# wireless-ac-motor-controller-mk-1_1.net
KiCad netlist of a schematic drawn in EAGLE
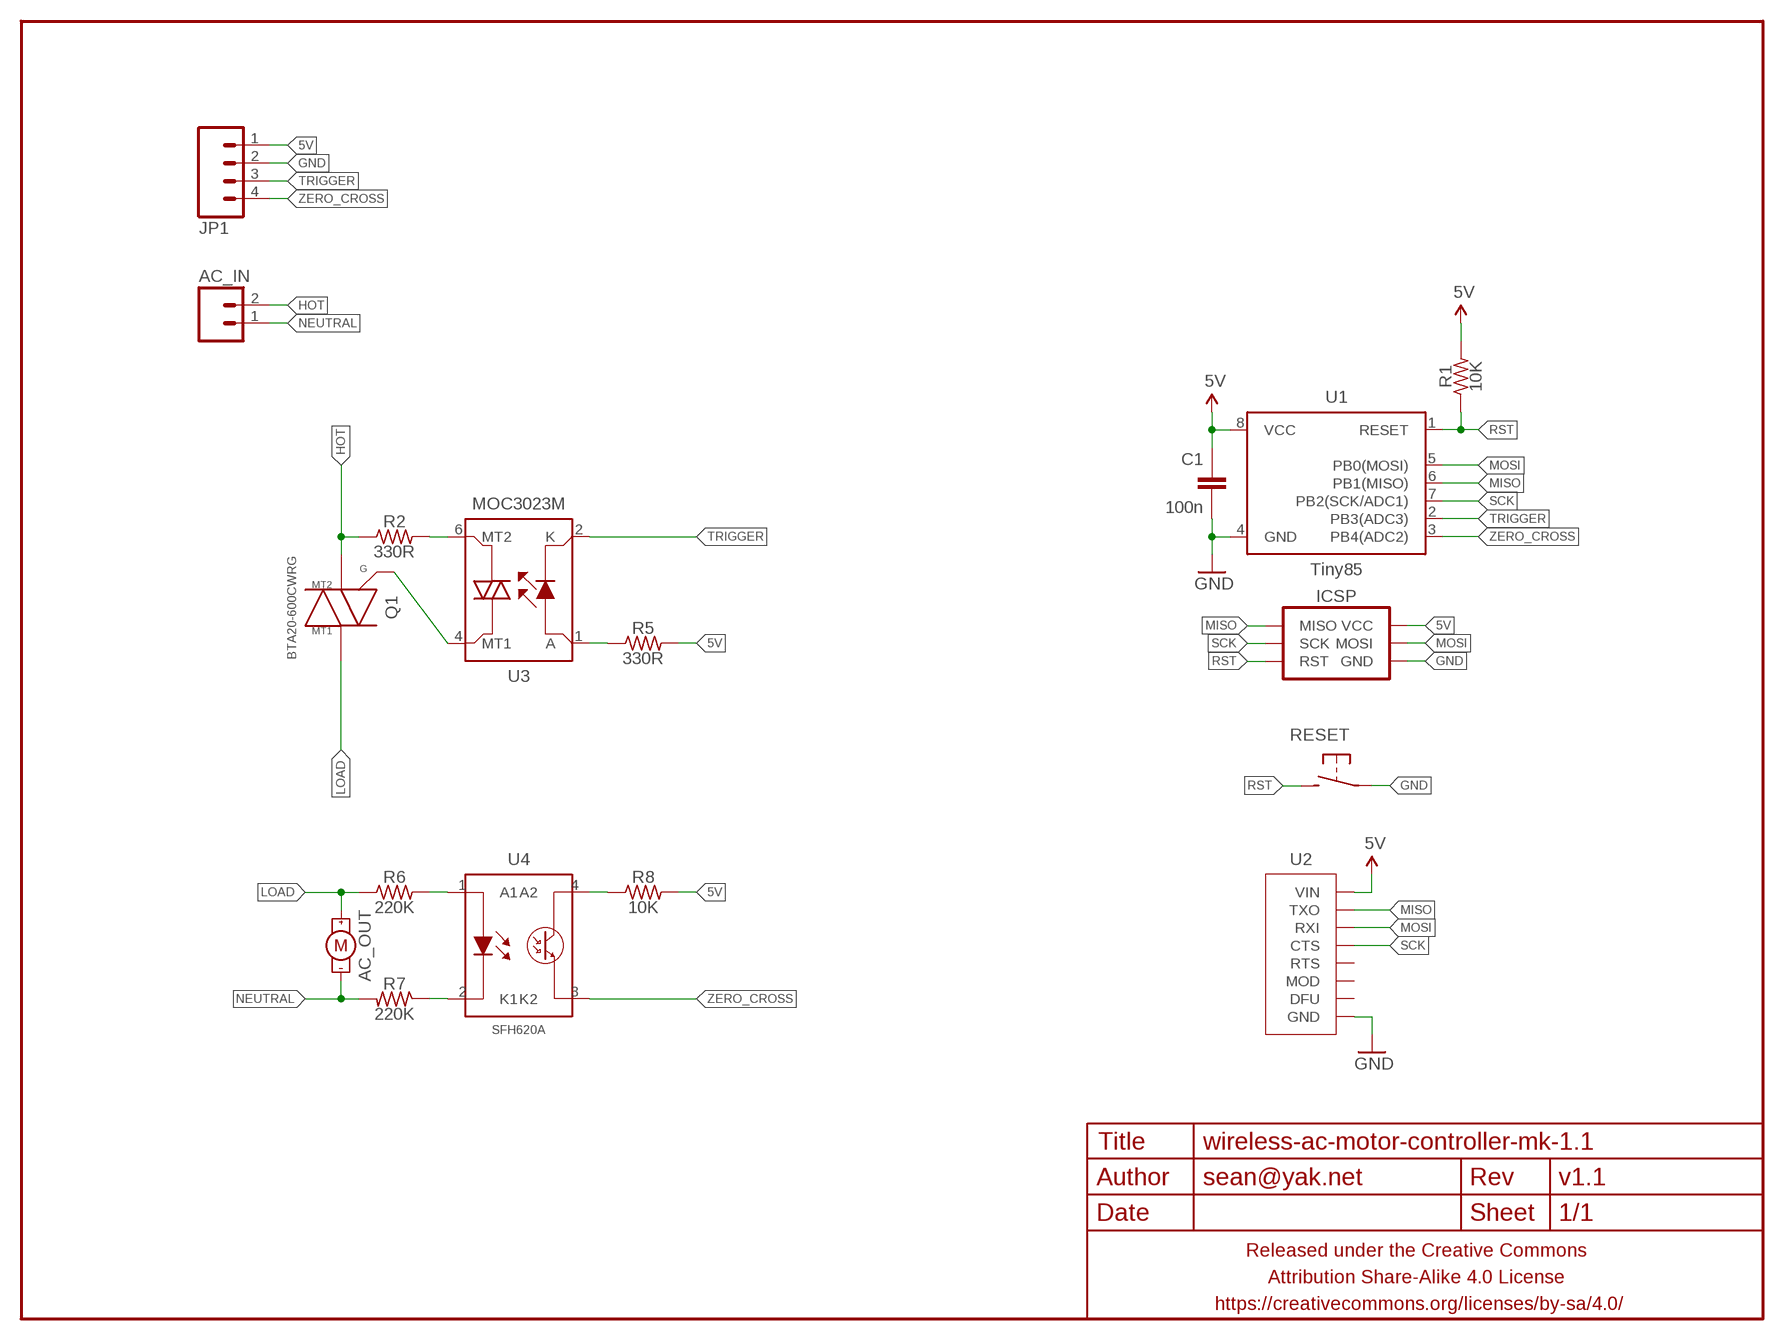
[diagram p0: schematic, sheet 1]

(export (version "E")
  (design (tool "Eeschema 10.0.6"))
  (components
    (comp (ref "AC_IN")
      (value "SCREWTERMINAL-25MM")
      (footprint "eagle-import:SCREWTERM-5MM-2")
      (libsource (lib "eagle-import") (part "SCREWTERMINAL-25MM"))
    )
    (comp (ref "AC_OUT")
      (value "MOTOR5MM-SCREW-TERM")
      (footprint "eagle-import:1X02_5MM_SCREW")
      (libsource (lib "eagle-import") (part "MOTOR5MM-SCREW-TERM"))
    )
    (comp (ref "C1")
      (value "100n")
      (footprint "eagle-import:C0805")
      (libsource (lib "eagle-import") (part "CAPACITOR-CERAMICC0805"))
    )
    (comp (ref "FRAME1")
      (value "FRAME-LETTERNO_PACKAGE")
      (footprint "eagle-import:DUMMY")
      (fields (field (name "DESIGNER") "sean@yak.net") (field (name "VERSION") "v1.1"))
      (libsource (lib "eagle-import") (part "FRAME-LETTERNO_PACKAGE"))
    )
    (comp (ref "ICSP")
      (value "AVR_SPI_PRG_6PTH")
      (footprint "eagle-import:2X3")
      (libsource (lib "eagle-import") (part "AVR_SPI_PRG_6PTH"))
    )
    (comp (ref "JP1")
      (value "M04JST-PTH-VERT")
      (footprint "eagle-import:JST-4-PH-VERT-PTH")
      (libsource (lib "eagle-import") (part "M04JST-PTH-VERT"))
    )
    (comp (ref "Q1")
      (value "BTA20-600CWRG")
      (footprint "eagle-import:TO220V")
      (libsource (lib "eagle-import") (part "TRIACTO-220-VERT"))
    )
    (comp (ref "R1")
      (value "10K")
      (footprint "eagle-import:R0805")
      (libsource (lib "eagle-import") (part "RESISTORR0805"))
    )
    (comp (ref "R2")
      (value "330R")
      (footprint "eagle-import:R0805")
      (libsource (lib "eagle-import") (part "RESISTORR0805"))
    )
    (comp (ref "R5")
      (value "330R")
      (footprint "eagle-import:R0805")
      (libsource (lib "eagle-import") (part "RESISTORR0805"))
    )
    (comp (ref "R6")
      (value "220K")
      (footprint "eagle-import:0411V")
      (libsource (lib "eagle-import") (part "RESISTOR0411/3V"))
    )
    (comp (ref "R7")
      (value "220K")
      (footprint "eagle-import:0411V")
      (libsource (lib "eagle-import") (part "RESISTOR0411/3V"))
    )
    (comp (ref "R8")
      (value "10K")
      (footprint "eagle-import:R0805")
      (libsource (lib "eagle-import") (part "RESISTORR0805"))
    )
    (comp (ref "RESET")
      (value "SPST-NO-TACT3MM-PTH-SMALL-PADS")
      (footprint "eagle-import:DTS-3-SMALL-PADS")
      (libsource (lib "eagle-import") (part "SPST-NO-TACT3MM-PTH-SMALL-PADS"))
    )
    (comp (ref "U1")
      (value "Tiny85")
      (footprint "eagle-import:SO08-EIAJ")
      (libsource (lib "eagle-import") (part "ATTINY45TINY85-20-SOICW"))
    )
    (comp (ref "U2")
      (value "ADAFRUIT_BLE_UARTBARE")
      (footprint "eagle-import:ADAFRUIT_BLE_UART")
      (libsource (lib "eagle-import") (part "ADAFRUIT_BLE_UARTBARE"))
    )
    (comp (ref "U3")
      (value "MOC3023M")
      (footprint "eagle-import:DIP06")
      (libsource (lib "eagle-import") (part "MOC30XXMOC30XXM-DIP6"))
    )
    (comp (ref "U4")
      (value "SFH620A")
      (footprint "eagle-import:DIL04")
      (libsource (lib "eagle-import") (part "OPTOISOLATORDIP4"))
    )
  )
  (nets
    (net (code "1") (name "5V") (class "Default")
      (node (ref "C1") (pin "1") (pinfunction "1_1") (pintype "passive"))
      (node (ref "ICSP") (pin "2") (pinfunction "VCC_2") (pintype "passive"))
      (node (ref "JP1") (pin "1") (pinfunction "1_1") (pintype "passive"))
      (node (ref "R1") (pin "2") (pinfunction "2_2") (pintype "passive"))
      (node (ref "R5") (pin "2") (pinfunction "2_2") (pintype "passive"))
      (node (ref "R8") (pin "2") (pinfunction "2_2") (pintype "passive"))
      (node (ref "U1") (pin "8") (pinfunction "VCC_8") (pintype "bidirectional"))
      (node (ref "U2") (pin "VIN") (pinfunction "VIN_VIN") (pintype "bidirectional"))
    )
    (net (code "2") (name "GND") (class "Default")
      (node (ref "C1") (pin "2") (pinfunction "2_2") (pintype "passive"))
      (node (ref "ICSP") (pin "6") (pinfunction "GND_6") (pintype "passive"))
      (node (ref "JP1") (pin "2") (pinfunction "2_2") (pintype "passive"))
      (node (ref "RESET") (pin "1") (pinfunction "1_1") (pintype "passive"))
      (node (ref "U1") (pin "4") (pinfunction "GND_4") (pintype "bidirectional"))
      (node (ref "U2") (pin "GND") (pinfunction "GND_GND") (pintype "bidirectional"))
    )
    (net (code "3") (name "HOT") (class "Default")
      (node (ref "AC_IN") (pin "2") (pinfunction "2_2") (pintype "passive"))
      (node (ref "Q1") (pin "2") (pinfunction "MT2_2") (pintype "bidirectional"))
      (node (ref "R2") (pin "1") (pinfunction "1_1") (pintype "passive"))
    )
    (net (code "4") (name "LOAD") (class "Default")
      (node (ref "AC_OUT") (pin "1") (pinfunction "+_1") (pintype "bidirectional"))
      (node (ref "Q1") (pin "1") (pinfunction "MT1_1") (pintype "bidirectional"))
      (node (ref "R6") (pin "1") (pinfunction "1_1") (pintype "passive"))
    )
    (net (code "5") (name "MISO") (class "Default")
      (node (ref "ICSP") (pin "1") (pinfunction "MISO_1") (pintype "passive"))
      (node (ref "U1") (pin "6") (pinfunction "PB1(MISO)_6") (pintype "bidirectional"))
      (node (ref "U2") (pin "TXO") (pinfunction "TXO_TXO") (pintype "bidirectional"))
    )
    (net (code "6") (name "MOSI") (class "Default")
      (node (ref "ICSP") (pin "4") (pinfunction "MOSI_4") (pintype "passive"))
      (node (ref "U1") (pin "5") (pinfunction "PB0(MOSI)_5") (pintype "bidirectional"))
      (node (ref "U2") (pin "RXI") (pinfunction "RXI_RXI") (pintype "bidirectional"))
    )
    (net (code "7") (name "NEUTRAL") (class "Default")
      (node (ref "AC_IN") (pin "1") (pinfunction "1_1") (pintype "passive"))
      (node (ref "AC_OUT") (pin "2") (pinfunction "-_2") (pintype "bidirectional"))
      (node (ref "R7") (pin "2") (pinfunction "2_2") (pintype "passive"))
    )
    (net (code "8") (name "Net-(Q1-GATE)") (class "Default")
      (node (ref "Q1") (pin "3") (pinfunction "GATE_3") (pintype "bidirectional"))
      (node (ref "U3") (pin "4") (pinfunction "MT1_4") (pintype "bidirectional"))
    )
    (net (code "9") (name "Net-(U3-A)") (class "Default")
      (node (ref "R5") (pin "1") (pinfunction "1_1") (pintype "passive"))
      (node (ref "U3") (pin "1") (pinfunction "A_1") (pintype "bidirectional"))
    )
    (net (code "10") (name "Net-(U3-MT2)") (class "Default")
      (node (ref "R2") (pin "2") (pinfunction "2_2") (pintype "passive"))
      (node (ref "U3") (pin "6") (pinfunction "MT2_6") (pintype "bidirectional"))
    )
    (net (code "11") (name "Net-(U4-A1)") (class "Default")
      (node (ref "R6") (pin "2") (pinfunction "2_2") (pintype "passive"))
      (node (ref "U4") (pin "1") (pinfunction "A1_1") (pintype "bidirectional"))
    )
    (net (code "12") (name "Net-(U4-A2)") (class "Default")
      (node (ref "R8") (pin "1") (pinfunction "1_1") (pintype "passive"))
      (node (ref "U4") (pin "4") (pinfunction "A2_4") (pintype "bidirectional"))
    )
    (net (code "13") (name "Net-(U4-K1)") (class "Default")
      (node (ref "R7") (pin "1") (pinfunction "1_1") (pintype "passive"))
      (node (ref "U4") (pin "2") (pinfunction "K1_2") (pintype "bidirectional"))
    )
    (net (code "14") (name "RST") (class "Default")
      (node (ref "ICSP") (pin "5") (pinfunction "RST_5") (pintype "passive"))
      (node (ref "R1") (pin "1") (pinfunction "1_1") (pintype "passive"))
      (node (ref "RESET") (pin "2") (pinfunction "2_2") (pintype "passive"))
      (node (ref "U1") (pin "1") (pinfunction "RESET_1") (pintype "bidirectional"))
    )
    (net (code "15") (name "SCK") (class "Default")
      (node (ref "ICSP") (pin "3") (pinfunction "SCK_3") (pintype "passive"))
      (node (ref "U1") (pin "7") (pinfunction "PB2(SCK/ADC1)_7") (pintype "bidirectional"))
      (node (ref "U2") (pin "CTS") (pinfunction "CTS_CTS") (pintype "bidirectional"))
    )
    (net (code "16") (name "TRIGGER") (class "Default")
      (node (ref "JP1") (pin "3") (pinfunction "3_3") (pintype "passive"))
      (node (ref "U1") (pin "2") (pinfunction "PB3(ADC3)_2") (pintype "bidirectional"))
      (node (ref "U3") (pin "2") (pinfunction "K_2") (pintype "bidirectional"))
    )
    (net (code "17") (name "ZERO_CROSS") (class "Default")
      (node (ref "JP1") (pin "4") (pinfunction "4_4") (pintype "passive"))
      (node (ref "U1") (pin "3") (pinfunction "PB4(ADC2)_3") (pintype "bidirectional"))
      (node (ref "U4") (pin "3") (pinfunction "K2_3") (pintype "bidirectional"))
    )
    (net (code "18") (name "unconnected-(U2-PadDFU)") (class "Default")
      (node (ref "U2") (pin "DFU") (pinfunction "DFU_DFU") (pintype "bidirectional"))
    )
    (net (code "19") (name "unconnected-(U2-PadMOD)") (class "Default")
      (node (ref "U2") (pin "MOD") (pinfunction "MOD_MOD") (pintype "bidirectional"))
    )
    (net (code "20") (name "unconnected-(U2-PadRTS)") (class "Default")
      (node (ref "U2") (pin "RTS") (pinfunction "RTS_RTS") (pintype "bidirectional"))
    )
  )
)
